# Bypass_FPGA_3V3.net
KiCad netlist of a schematic drawn in Altium Designer
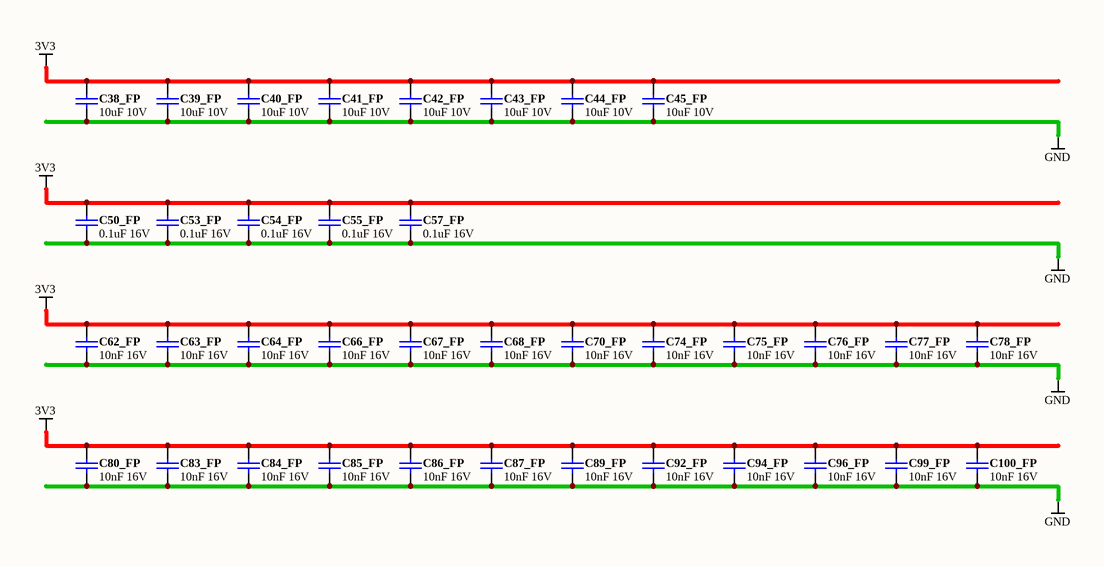
[diagram p0: Bypass_FPGA_3V3.SchDoc]

(export (version "E")
  (design (tool "Eeschema 10.0.6"))
  (components
    (comp (ref "C38_FP")
      (value "10uF 10V")
      (footprint "CAPC2012-STAR")
      (description "Capacitor, Ceramic, 10uF 10% 10V 0805 (2012) X5R")
      (fields (field (name "TOLERANCE") "10 %"))
      (libsource (lib "AltiumDesignLibrary") (part "CAP-NP"))
    )
    (comp (ref "C39_FP")
      (value "10uF 10V")
      (footprint "CAPC2012-STAR")
      (description "Capacitor, Ceramic, 10uF 10% 10V 0805 (2012) X5R")
      (fields (field (name "TOLERANCE") "10 %"))
      (libsource (lib "AltiumDesignLibrary") (part "CAP-NP"))
    )
    (comp (ref "C40_FP")
      (value "10uF 10V")
      (footprint "CAPC2012-STAR")
      (description "Capacitor, Ceramic, 10uF 10% 10V 0805 (2012) X5R")
      (fields (field (name "TOLERANCE") "10 %"))
      (libsource (lib "AltiumDesignLibrary") (part "CAP-NP"))
    )
    (comp (ref "C41_FP")
      (value "10uF 10V")
      (footprint "CAPC2012-STAR")
      (description "Capacitor, Ceramic, 10uF 10% 10V 0805 (2012) X5R")
      (fields (field (name "TOLERANCE") "10 %"))
      (libsource (lib "AltiumDesignLibrary") (part "CAP-NP"))
    )
    (comp (ref "C42_FP")
      (value "10uF 10V")
      (footprint "CAPC2012-STAR")
      (description "Capacitor, Ceramic, 10uF 10% 10V 0805 (2012) X5R")
      (fields (field (name "TOLERANCE") "10 %"))
      (libsource (lib "AltiumDesignLibrary") (part "CAP-NP"))
    )
    (comp (ref "C43_FP")
      (value "10uF 10V")
      (footprint "CAPC2012-STAR")
      (description "Capacitor, Ceramic, 10uF 10% 10V 0805 (2012) X5R")
      (fields (field (name "TOLERANCE") "10 %"))
      (libsource (lib "AltiumDesignLibrary") (part "CAP-NP"))
    )
    (comp (ref "C44_FP")
      (value "10uF 10V")
      (footprint "CAPC2012-STAR")
      (description "Capacitor, Ceramic, 10uF 10% 10V 0805 (2012) X5R")
      (fields (field (name "TOLERANCE") "10 %"))
      (libsource (lib "AltiumDesignLibrary") (part "CAP-NP"))
    )
    (comp (ref "C45_FP")
      (value "10uF 10V")
      (footprint "CAPC2012-STAR")
      (description "Capacitor, Ceramic, 10uF 10% 10V 0805 (2012) X5R")
      (fields (field (name "TOLERANCE") "10 %"))
      (libsource (lib "AltiumDesignLibrary") (part "CAP-NP"))
    )
    (comp (ref "C50_FP")
      (value "0.1uF 16V")
      (footprint "CAPC1005-STAR")
      (description "Capacitor, Ceramic, 0.1uF 10% 16V 0402 (1005) X7R")
      (fields (field (name "TOLERANCE") "10 %"))
      (libsource (lib "AltiumDesignLibrary") (part "CAP-NP"))
    )
    (comp (ref "C53_FP")
      (value "0.1uF 16V")
      (footprint "CAPC1005-STAR")
      (description "Capacitor, Ceramic, 0.1uF 10% 16V 0402 (1005) X7R")
      (fields (field (name "TOLERANCE") "10 %"))
      (libsource (lib "AltiumDesignLibrary") (part "CAP-NP"))
    )
    (comp (ref "C54_FP")
      (value "0.1uF 16V")
      (footprint "CAPC1005-STAR")
      (description "Capacitor, Ceramic, 0.1uF 10% 16V 0402 (1005) X7R")
      (fields (field (name "TOLERANCE") "10 %"))
      (libsource (lib "AltiumDesignLibrary") (part "CAP-NP"))
    )
    (comp (ref "C55_FP")
      (value "0.1uF 16V")
      (footprint "CAPC1005-STAR")
      (description "Capacitor, Ceramic, 0.1uF 10% 16V 0402 (1005) X7R")
      (fields (field (name "TOLERANCE") "10 %"))
      (libsource (lib "AltiumDesignLibrary") (part "CAP-NP"))
    )
    (comp (ref "C57_FP")
      (value "0.1uF 16V")
      (footprint "CAPC1005-STAR")
      (description "Capacitor, Ceramic, 0.1uF 10% 16V 0402 (1005) X7R")
      (fields (field (name "TOLERANCE") "10 %"))
      (libsource (lib "AltiumDesignLibrary") (part "CAP-NP"))
    )
    (comp (ref "C62_FP")
      (value "10nF 16V")
      (footprint "CAPC1005-STAR")
      (description "Capacitor, Ceramic, 10nF 10% 16V 0402 (1005) X7R")
      (fields (field (name "TOLERANCE") "10 %"))
      (libsource (lib "AltiumDesignLibrary") (part "CAP-NP"))
    )
    (comp (ref "C63_FP")
      (value "10nF 16V")
      (footprint "CAPC1005-STAR")
      (description "Capacitor, Ceramic, 10nF 10% 16V 0402 (1005) X7R")
      (fields (field (name "TOLERANCE") "10 %"))
      (libsource (lib "AltiumDesignLibrary") (part "CAP-NP"))
    )
    (comp (ref "C64_FP")
      (value "10nF 16V")
      (footprint "CAPC1005-STAR")
      (description "Capacitor, Ceramic, 10nF 10% 16V 0402 (1005) X7R")
      (fields (field (name "TOLERANCE") "10 %"))
      (libsource (lib "AltiumDesignLibrary") (part "CAP-NP"))
    )
    (comp (ref "C66_FP")
      (value "10nF 16V")
      (footprint "CAPC1005-STAR")
      (description "Capacitor, Ceramic, 10nF 10% 16V 0402 (1005) X7R")
      (fields (field (name "TOLERANCE") "10 %"))
      (libsource (lib "AltiumDesignLibrary") (part "CAP-NP"))
    )
    (comp (ref "C67_FP")
      (value "10nF 16V")
      (footprint "CAPC1005-STAR")
      (description "Capacitor, Ceramic, 10nF 10% 16V 0402 (1005) X7R")
      (fields (field (name "TOLERANCE") "10 %"))
      (libsource (lib "AltiumDesignLibrary") (part "CAP-NP"))
    )
    (comp (ref "C68_FP")
      (value "10nF 16V")
      (footprint "CAPC1005-STAR")
      (description "Capacitor, Ceramic, 10nF 10% 16V 0402 (1005) X7R")
      (fields (field (name "TOLERANCE") "10 %"))
      (libsource (lib "AltiumDesignLibrary") (part "CAP-NP"))
    )
    (comp (ref "C70_FP")
      (value "10nF 16V")
      (footprint "CAPC1005-STAR")
      (description "Capacitor, Ceramic, 10nF 10% 16V 0402 (1005) X7R")
      (fields (field (name "TOLERANCE") "10 %"))
      (libsource (lib "AltiumDesignLibrary") (part "CAP-NP"))
    )
    (comp (ref "C74_FP")
      (value "10nF 16V")
      (footprint "CAPC1005-STAR")
      (description "Capacitor, Ceramic, 10nF 10% 16V 0402 (1005) X7R")
      (fields (field (name "TOLERANCE") "10 %"))
      (libsource (lib "AltiumDesignLibrary") (part "CAP-NP"))
    )
    (comp (ref "C75_FP")
      (value "10nF 16V")
      (footprint "CAPC1005-STAR")
      (description "Capacitor, Ceramic, 10nF 10% 16V 0402 (1005) X7R")
      (fields (field (name "TOLERANCE") "10 %"))
      (libsource (lib "AltiumDesignLibrary") (part "CAP-NP"))
    )
    (comp (ref "C76_FP")
      (value "10nF 16V")
      (footprint "CAPC1005-STAR")
      (description "Capacitor, Ceramic, 10nF 10% 16V 0402 (1005) X7R")
      (fields (field (name "TOLERANCE") "10 %"))
      (libsource (lib "AltiumDesignLibrary") (part "CAP-NP"))
    )
    (comp (ref "C77_FP")
      (value "10nF 16V")
      (footprint "CAPC1005-STAR")
      (description "Capacitor, Ceramic, 10nF 10% 16V 0402 (1005) X7R")
      (fields (field (name "TOLERANCE") "10 %"))
      (libsource (lib "AltiumDesignLibrary") (part "CAP-NP"))
    )
    (comp (ref "C78_FP")
      (value "10nF 16V")
      (footprint "CAPC1005-STAR")
      (description "Capacitor, Ceramic, 10nF 10% 16V 0402 (1005) X7R")
      (fields (field (name "TOLERANCE") "10 %"))
      (libsource (lib "AltiumDesignLibrary") (part "CAP-NP"))
    )
    (comp (ref "C80_FP")
      (value "10nF 16V")
      (footprint "CAPC1005-STAR")
      (description "Capacitor, Ceramic, 10nF 10% 16V 0402 (1005) X7R")
      (fields (field (name "TOLERANCE") "10 %"))
      (libsource (lib "AltiumDesignLibrary") (part "CAP-NP"))
    )
    (comp (ref "C83_FP")
      (value "10nF 16V")
      (footprint "CAPC1005-STAR")
      (description "Capacitor, Ceramic, 10nF 10% 16V 0402 (1005) X7R")
      (fields (field (name "TOLERANCE") "10 %"))
      (libsource (lib "AltiumDesignLibrary") (part "CAP-NP"))
    )
    (comp (ref "C84_FP")
      (value "10nF 16V")
      (footprint "CAPC1005-STAR")
      (description "Capacitor, Ceramic, 10nF 10% 16V 0402 (1005) X7R")
      (fields (field (name "TOLERANCE") "10 %"))
      (libsource (lib "AltiumDesignLibrary") (part "CAP-NP"))
    )
    (comp (ref "C85_FP")
      (value "10nF 16V")
      (footprint "CAPC1005-STAR")
      (description "Capacitor, Ceramic, 10nF 10% 16V 0402 (1005) X7R")
      (fields (field (name "TOLERANCE") "10 %"))
      (libsource (lib "AltiumDesignLibrary") (part "CAP-NP"))
    )
    (comp (ref "C86_FP")
      (value "10nF 16V")
      (footprint "CAPC1005-STAR")
      (description "Capacitor, Ceramic, 10nF 10% 16V 0402 (1005) X7R")
      (fields (field (name "TOLERANCE") "10 %"))
      (libsource (lib "AltiumDesignLibrary") (part "CAP-NP"))
    )
    (comp (ref "C87_FP")
      (value "10nF 16V")
      (footprint "CAPC1005-STAR")
      (description "Capacitor, Ceramic, 10nF 10% 16V 0402 (1005) X7R")
      (fields (field (name "TOLERANCE") "10 %"))
      (libsource (lib "AltiumDesignLibrary") (part "CAP-NP"))
    )
    (comp (ref "C89_FP")
      (value "10nF 16V")
      (footprint "CAPC1005-STAR")
      (description "Capacitor, Ceramic, 10nF 10% 16V 0402 (1005) X7R")
      (fields (field (name "TOLERANCE") "10 %"))
      (libsource (lib "AltiumDesignLibrary") (part "CAP-NP"))
    )
    (comp (ref "C92_FP")
      (value "10nF 16V")
      (footprint "CAPC1005-STAR")
      (description "Capacitor, Ceramic, 10nF 10% 16V 0402 (1005) X7R")
      (fields (field (name "TOLERANCE") "10 %"))
      (libsource (lib "AltiumDesignLibrary") (part "CAP-NP"))
    )
    (comp (ref "C94_FP")
      (value "10nF 16V")
      (footprint "CAPC1005-STAR")
      (description "Capacitor, Ceramic, 10nF 10% 16V 0402 (1005) X7R")
      (fields (field (name "TOLERANCE") "10 %"))
      (libsource (lib "AltiumDesignLibrary") (part "CAP-NP"))
    )
    (comp (ref "C96_FP")
      (value "10nF 16V")
      (footprint "CAPC1005-STAR")
      (description "Capacitor, Ceramic, 10nF 10% 16V 0402 (1005) X7R")
      (fields (field (name "TOLERANCE") "10 %"))
      (libsource (lib "AltiumDesignLibrary") (part "CAP-NP"))
    )
    (comp (ref "C99_FP")
      (value "10nF 16V")
      (footprint "CAPC1005-STAR")
      (description "Capacitor, Ceramic, 10nF 10% 16V 0402 (1005) X7R")
      (fields (field (name "TOLERANCE") "10 %"))
      (libsource (lib "AltiumDesignLibrary") (part "CAP-NP"))
    )
    (comp (ref "C100_FP")
      (value "10nF 16V")
      (footprint "CAPC1005-STAR")
      (description "Capacitor, Ceramic, 10nF 10% 16V 0402 (1005) X7R")
      (fields (field (name "TOLERANCE") "10 %"))
      (libsource (lib "AltiumDesignLibrary") (part "CAP-NP"))
    )
  )
  (nets
    (net (code "1") (name "3V3") (class "Default")
      (node (ref "C100_FP") (pin "1") (pinfunction "1_1") (pintype "passive"))
      (node (ref "C38_FP") (pin "1") (pinfunction "1_1") (pintype "passive"))
      (node (ref "C39_FP") (pin "1") (pinfunction "1_1") (pintype "passive"))
      (node (ref "C40_FP") (pin "1") (pinfunction "1_1") (pintype "passive"))
      (node (ref "C41_FP") (pin "1") (pinfunction "1_1") (pintype "passive"))
      (node (ref "C42_FP") (pin "1") (pinfunction "1_1") (pintype "passive"))
      (node (ref "C43_FP") (pin "1") (pinfunction "1_1") (pintype "passive"))
      (node (ref "C44_FP") (pin "1") (pinfunction "1_1") (pintype "passive"))
      (node (ref "C45_FP") (pin "1") (pinfunction "1_1") (pintype "passive"))
      (node (ref "C50_FP") (pin "1") (pinfunction "1_1") (pintype "passive"))
      (node (ref "C53_FP") (pin "1") (pinfunction "1_1") (pintype "passive"))
      (node (ref "C54_FP") (pin "1") (pinfunction "1_1") (pintype "passive"))
      (node (ref "C55_FP") (pin "1") (pinfunction "1_1") (pintype "passive"))
      (node (ref "C57_FP") (pin "1") (pinfunction "1_1") (pintype "passive"))
      (node (ref "C62_FP") (pin "1") (pinfunction "1_1") (pintype "passive"))
      (node (ref "C63_FP") (pin "1") (pinfunction "1_1") (pintype "passive"))
      (node (ref "C64_FP") (pin "1") (pinfunction "1_1") (pintype "passive"))
      (node (ref "C66_FP") (pin "1") (pinfunction "1_1") (pintype "passive"))
      (node (ref "C67_FP") (pin "1") (pinfunction "1_1") (pintype "passive"))
      (node (ref "C68_FP") (pin "1") (pinfunction "1_1") (pintype "passive"))
      (node (ref "C70_FP") (pin "1") (pinfunction "1_1") (pintype "passive"))
      (node (ref "C74_FP") (pin "1") (pinfunction "1_1") (pintype "passive"))
      (node (ref "C75_FP") (pin "1") (pinfunction "1_1") (pintype "passive"))
      (node (ref "C76_FP") (pin "1") (pinfunction "1_1") (pintype "passive"))
      (node (ref "C77_FP") (pin "1") (pinfunction "1_1") (pintype "passive"))
      (node (ref "C78_FP") (pin "1") (pinfunction "1_1") (pintype "passive"))
      (node (ref "C80_FP") (pin "1") (pinfunction "1_1") (pintype "passive"))
      (node (ref "C83_FP") (pin "1") (pinfunction "1_1") (pintype "passive"))
      (node (ref "C84_FP") (pin "1") (pinfunction "1_1") (pintype "passive"))
      (node (ref "C85_FP") (pin "1") (pinfunction "1_1") (pintype "passive"))
      (node (ref "C86_FP") (pin "1") (pinfunction "1_1") (pintype "passive"))
      (node (ref "C87_FP") (pin "1") (pinfunction "1_1") (pintype "passive"))
      (node (ref "C89_FP") (pin "1") (pinfunction "1_1") (pintype "passive"))
      (node (ref "C92_FP") (pin "1") (pinfunction "1_1") (pintype "passive"))
      (node (ref "C94_FP") (pin "1") (pinfunction "1_1") (pintype "passive"))
      (node (ref "C96_FP") (pin "1") (pinfunction "1_1") (pintype "passive"))
      (node (ref "C99_FP") (pin "1") (pinfunction "1_1") (pintype "passive"))
    )
    (net (code "2") (name "GND") (class "Default")
      (node (ref "C100_FP") (pin "2") (pinfunction "2_2") (pintype "passive"))
      (node (ref "C38_FP") (pin "2") (pinfunction "2_2") (pintype "passive"))
      (node (ref "C39_FP") (pin "2") (pinfunction "2_2") (pintype "passive"))
      (node (ref "C40_FP") (pin "2") (pinfunction "2_2") (pintype "passive"))
      (node (ref "C41_FP") (pin "2") (pinfunction "2_2") (pintype "passive"))
      (node (ref "C42_FP") (pin "2") (pinfunction "2_2") (pintype "passive"))
      (node (ref "C43_FP") (pin "2") (pinfunction "2_2") (pintype "passive"))
      (node (ref "C44_FP") (pin "2") (pinfunction "2_2") (pintype "passive"))
      (node (ref "C45_FP") (pin "2") (pinfunction "2_2") (pintype "passive"))
      (node (ref "C50_FP") (pin "2") (pinfunction "2_2") (pintype "passive"))
      (node (ref "C53_FP") (pin "2") (pinfunction "2_2") (pintype "passive"))
      (node (ref "C54_FP") (pin "2") (pinfunction "2_2") (pintype "passive"))
      (node (ref "C55_FP") (pin "2") (pinfunction "2_2") (pintype "passive"))
      (node (ref "C57_FP") (pin "2") (pinfunction "2_2") (pintype "passive"))
      (node (ref "C62_FP") (pin "2") (pinfunction "2_2") (pintype "passive"))
      (node (ref "C63_FP") (pin "2") (pinfunction "2_2") (pintype "passive"))
      (node (ref "C64_FP") (pin "2") (pinfunction "2_2") (pintype "passive"))
      (node (ref "C66_FP") (pin "2") (pinfunction "2_2") (pintype "passive"))
      (node (ref "C67_FP") (pin "2") (pinfunction "2_2") (pintype "passive"))
      (node (ref "C68_FP") (pin "2") (pinfunction "2_2") (pintype "passive"))
      (node (ref "C70_FP") (pin "2") (pinfunction "2_2") (pintype "passive"))
      (node (ref "C74_FP") (pin "2") (pinfunction "2_2") (pintype "passive"))
      (node (ref "C75_FP") (pin "2") (pinfunction "2_2") (pintype "passive"))
      (node (ref "C76_FP") (pin "2") (pinfunction "2_2") (pintype "passive"))
      (node (ref "C77_FP") (pin "2") (pinfunction "2_2") (pintype "passive"))
      (node (ref "C78_FP") (pin "2") (pinfunction "2_2") (pintype "passive"))
      (node (ref "C80_FP") (pin "2") (pinfunction "2_2") (pintype "passive"))
      (node (ref "C83_FP") (pin "2") (pinfunction "2_2") (pintype "passive"))
      (node (ref "C84_FP") (pin "2") (pinfunction "2_2") (pintype "passive"))
      (node (ref "C85_FP") (pin "2") (pinfunction "2_2") (pintype "passive"))
      (node (ref "C86_FP") (pin "2") (pinfunction "2_2") (pintype "passive"))
      (node (ref "C87_FP") (pin "2") (pinfunction "2_2") (pintype "passive"))
      (node (ref "C89_FP") (pin "2") (pinfunction "2_2") (pintype "passive"))
      (node (ref "C92_FP") (pin "2") (pinfunction "2_2") (pintype "passive"))
      (node (ref "C94_FP") (pin "2") (pinfunction "2_2") (pintype "passive"))
      (node (ref "C96_FP") (pin "2") (pinfunction "2_2") (pintype "passive"))
      (node (ref "C99_FP") (pin "2") (pinfunction "2_2") (pintype "passive"))
    )
  )
)
